# final.net
KiCad netlist of a schematic drawn in Altium Designer
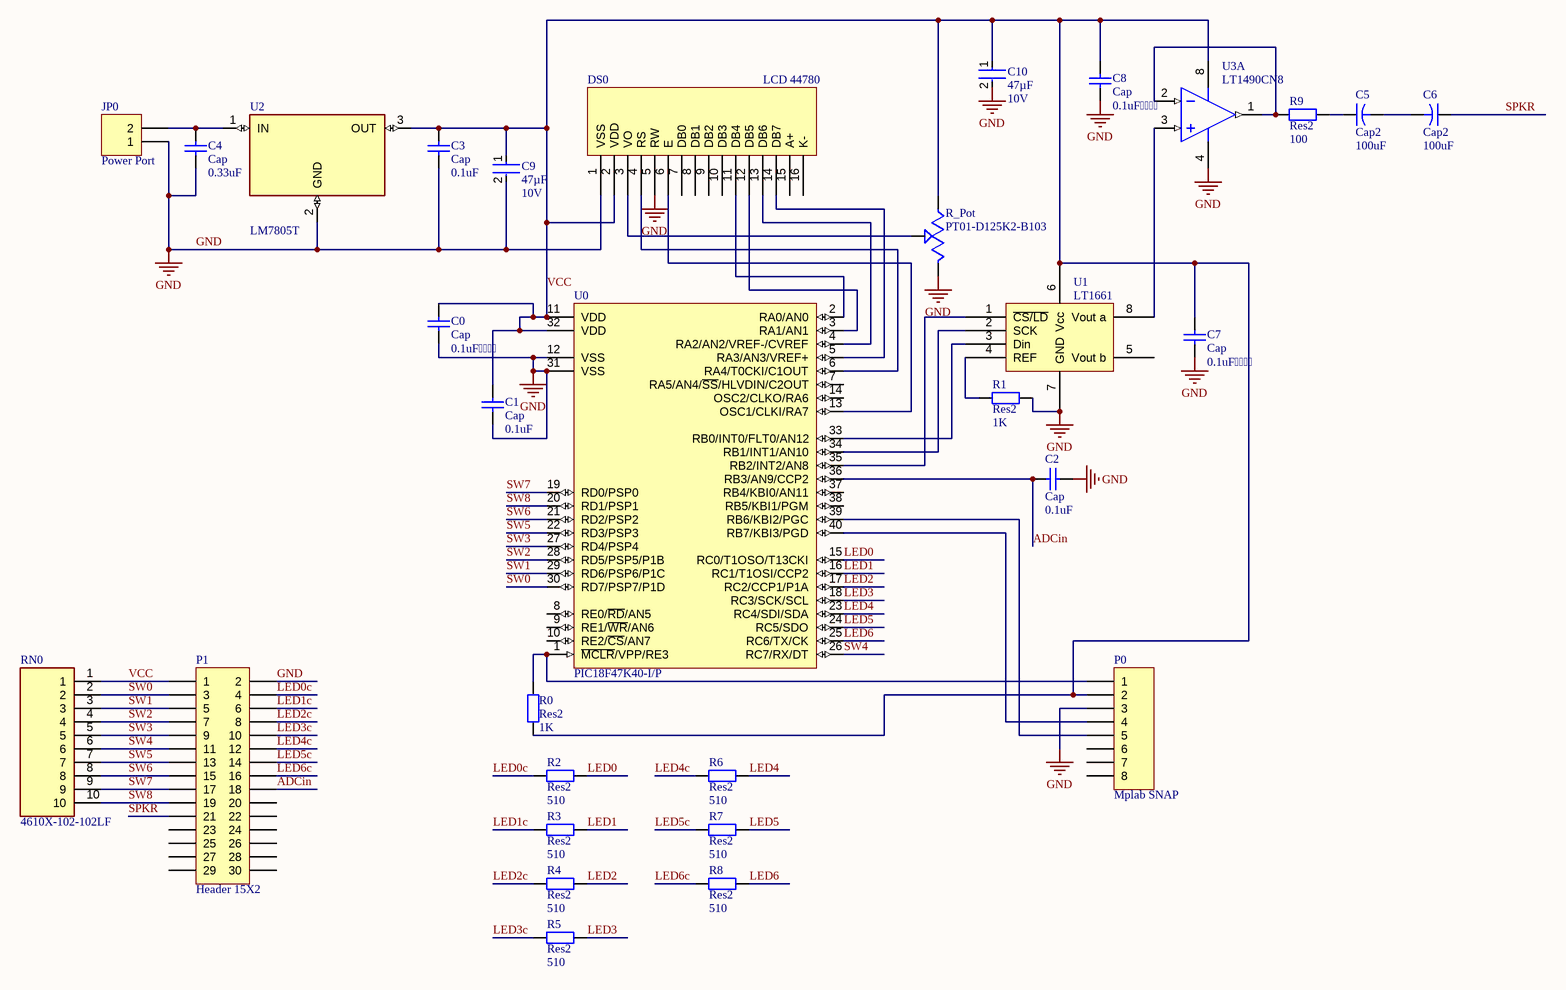
[diagram p0: final.SchDoc]

(export (version "E")
  (design (tool "Eeschema 10.0.6"))
  (components
    (comp (ref "C0")
      (value "Cap")
      (footprint "RAD-0.3")
      (description "Capacitor")
      (fields (field (name "ALTIUM_VALUE") "0.1uF") (field (name "PUBLISHER") "Altium Limited"))
      (libsource (lib "Miscellaneous Devices") (part "Cap"))
    )
    (comp (ref "C1")
      (value "Cap")
      (footprint "RAD-0.3")
      (description "Capacitor")
      (fields (field (name "ALTIUM_VALUE") "0.1uF") (field (name "PUBLISHER") "Altium Limited"))
      (libsource (lib "Miscellaneous Devices") (part "Cap"))
    )
    (comp (ref "C2")
      (value "Cap")
      (footprint "RAD-0.3")
      (description "Capacitor")
      (fields (field (name "ALTIUM_VALUE") "0.1uF") (field (name "PUBLISHER") "Altium Limited"))
      (libsource (lib "Miscellaneous Devices") (part "Cap"))
    )
    (comp (ref "C3")
      (value "Cap")
      (footprint "RAD-0.3")
      (description "Capacitor")
      (fields (field (name "ALTIUM_VALUE") "0.1uF") (field (name "PUBLISHER") "Altium Limited"))
      (libsource (lib "Miscellaneous Devices") (part "Cap"))
    )
    (comp (ref "C4")
      (value "Cap")
      (footprint "RAD-0.3")
      (description "Capacitor")
      (fields (field (name "ALTIUM_VALUE") "0.33uF") (field (name "PUBLISHER") "Altium Limited"))
      (libsource (lib "Miscellaneous Devices") (part "Cap"))
    )
    (comp (ref "C5")
      (value "Cap2")
      (footprint "CAPR5-4X5")
      (description "Capacitor")
      (fields (field (name "ALTIUM_VALUE") "100uF") (field (name "PUBLISHER") "Altium Limited"))
      (libsource (lib "Miscellaneous Devices") (part "Cap2"))
    )
    (comp (ref "C6")
      (value "Cap2")
      (footprint "CAPR5-4X5")
      (description "Capacitor")
      (fields (field (name "ALTIUM_VALUE") "100uF") (field (name "PUBLISHER") "Altium Limited"))
      (libsource (lib "Miscellaneous Devices") (part "Cap2"))
    )
    (comp (ref "C7")
      (value "Cap")
      (footprint "RAD-0.3")
      (description "Capacitor")
      (fields (field (name "ALTIUM_VALUE") "0.1uF") (field (name "PUBLISHER") "Altium Limited"))
      (libsource (lib "Miscellaneous Devices") (part "Cap"))
    )
    (comp (ref "C8")
      (value "Cap")
      (footprint "RAD-0.3")
      (description "Capacitor")
      (fields (field (name "ALTIUM_VALUE") "0.1uF") (field (name "PUBLISHER") "Altium Limited"))
      (libsource (lib "Miscellaneous Devices") (part "Cap"))
    )
    (comp (ref "C9")
      (value "Cap_Kemet_C1206C476M8PACTU_eec")
      (footprint "Kemet_C1206C476M8PACTU_0")
      (description "CAP 47µF ±20% 10V Ceramic Capacitor X5R 1206 (3216 Metric)")
      (fields
        (field (name "CAPACITANCE") "47µF")
        (field (name "VOLTAGE") "10V")
        (field (name "PART NUMBER") "C1206C476M8PACTU")
        (field (name "MANUFACTURER") "Kemet")
      )
      (libsource (lib "Cap_Kemet_C1206C476M8PACTU_eec") (part "Cap_Kemet_C1206C476M8PACTU_eec"))
    )
    (comp (ref "C10")
      (value "Cap_Kemet_C1206C476M8PACTU_eec")
      (footprint "Kemet_C1206C476M8PACTU_0")
      (description "CAP 47µF ±20% 10V Ceramic Capacitor X5R 1206 (3216 Metric)")
      (fields
        (field (name "CAPACITANCE") "47µF")
        (field (name "VOLTAGE") "10V")
        (field (name "PART NUMBER") "C1206C476M8PACTU")
        (field (name "MANUFACTURER") "Kemet")
      )
      (libsource (lib "Cap_Kemet_C1206C476M8PACTU_eec") (part "Cap_Kemet_C1206C476M8PACTU_eec"))
    )
    (comp (ref "DS0")
      (value "LCD 44780")
      (footprint "OLED 16x2")
      (libsource (lib "ECE LIB 21") (part "LCD 44780"))
    )
    (comp (ref "JP0")
      (value "Power Port")
      (footprint "CON2screw")
      (libsource (lib "ECE LIB 21") (part "Power"))
    )
    (comp (ref "P0")
      (value "Mplab SNAP")
      (footprint "HDR1X8")
      (description "Header, 8-Pin")
      (fields (field (name "PUBLISHER") "Altium Limited"))
      (libsource (lib "ECE LIB 21") (part "Header 8"))
    )
    (comp (ref "P1")
      (value "Header 15X2")
      (footprint "HDR2X15")
      (description "Header, 15-Pin, Dual row")
      (fields (field (name "PUBLISHER") "Altium Limited"))
      (libsource (lib "Miscellaneous Connectors") (part "Header 15X2"))
    )
    (comp (ref "R0")
      (value "Res2")
      (footprint "AXIAL-0.4")
      (description "Resistor")
      (fields (field (name "ALTIUM_VALUE") "1K") (field (name "PUBLISHER") "Altium Limited"))
      (libsource (lib "") (part "Res2_1"))
    )
    (comp (ref "R1")
      (value "Res2")
      (footprint "AXIAL-0.4")
      (description "Resistor")
      (fields (field (name "ALTIUM_VALUE") "1K") (field (name "PUBLISHER") "Altium Limited"))
      (libsource (lib "Miscellaneous Devices") (part "Res2"))
    )
    (comp (ref "R2")
      (value "Res2")
      (footprint "AXIAL-0.4")
      (description "Resistor")
      (fields (field (name "ALTIUM_VALUE") "510") (field (name "PUBLISHER") "Altium Limited"))
      (libsource (lib "Miscellaneous Devices") (part "Res2"))
    )
    (comp (ref "R3")
      (value "Res2")
      (footprint "AXIAL-0.4")
      (description "Resistor")
      (fields (field (name "ALTIUM_VALUE") "510") (field (name "PUBLISHER") "Altium Limited"))
      (libsource (lib "Miscellaneous Devices") (part "Res2"))
    )
    (comp (ref "R4")
      (value "Res2")
      (footprint "AXIAL-0.4")
      (description "Resistor")
      (fields (field (name "ALTIUM_VALUE") "510") (field (name "PUBLISHER") "Altium Limited"))
      (libsource (lib "Miscellaneous Devices") (part "Res2"))
    )
    (comp (ref "R5")
      (value "Res2")
      (footprint "AXIAL-0.4")
      (description "Resistor")
      (fields (field (name "ALTIUM_VALUE") "510") (field (name "PUBLISHER") "Altium Limited"))
      (libsource (lib "Miscellaneous Devices") (part "Res2"))
    )
    (comp (ref "R6")
      (value "Res2")
      (footprint "AXIAL-0.4")
      (description "Resistor")
      (fields (field (name "ALTIUM_VALUE") "510") (field (name "PUBLISHER") "Altium Limited"))
      (libsource (lib "Miscellaneous Devices") (part "Res2"))
    )
    (comp (ref "R7")
      (value "Res2")
      (footprint "AXIAL-0.4")
      (description "Resistor")
      (fields (field (name "ALTIUM_VALUE") "510") (field (name "PUBLISHER") "Altium Limited"))
      (libsource (lib "Miscellaneous Devices") (part "Res2"))
    )
    (comp (ref "R8")
      (value "Res2")
      (footprint "AXIAL-0.4")
      (description "Resistor")
      (fields (field (name "ALTIUM_VALUE") "510") (field (name "PUBLISHER") "Altium Limited"))
      (libsource (lib "Miscellaneous Devices") (part "Res2"))
    )
    (comp (ref "R9")
      (value "Res2")
      (footprint "AXIAL-0.4")
      (description "Resistor")
      (fields (field (name "ALTIUM_VALUE") "100") (field (name "PUBLISHER") "Altium Limited"))
      (libsource (lib "Miscellaneous Devices") (part "Res2"))
    )
    (comp (ref "RN0")
      (value "4610X-102-102LF")
      (footprint "SamacSys:SIP249W51P254L2535H508Q10P")
      (description "Resistor Network")
      (fields (field (name "MOUSER PART NUMBER") "652-4610X-2LF-1K"))
      (libsource (lib "*") (part "4610X-102-102LF"))
    )
    (comp (ref "R_Pot")
      (value "PT01-D125K2-B103")
      (footprint "TRIM_PT01-D125K2-B103")
      (description "10k Ohm 1 Gang Linear Through Hole Potentiometer None 1.0 Kierros Carbon 0.05W, 1/20W PC Pins")
      (fields (field (name "MF") "CUI Devices"))
      (libsource (lib "PT01-D125K2-B103") (part "PT01-D125K2-B103"))
    )
    (comp (ref "U0")
      (value "PIC18F47K40-I/P")
      (footprint "DIP-40")
      (libsource (lib "ECE LIB 21") (part "PIC18F4620-I/P_1"))
    )
    (comp (ref "U1") (value "LT1661") (footprint "LT-N8") (libsource (lib "ECE LIB 21") (part "LT1661")))
    (comp (ref "U2")
      (value "LM7805T")
      (footprint "TO220")
      (fields (field (name "MF") "Texas Instruments"))
      (libsource (lib "LM7805T") (part "LM7805T"))
    )
    (comp (ref "U3")
      (value "LT1490CN8")
      (footprint "LT-N8-8")
      (fields
        (field (name "LINEAR TECHNOLOGY PART NUMBER") "LT1490A")
        (field (name "MANUFACTURER") "Linear Technology")
      )
      (libsource (lib "Linear Technology Operational Amplifiers (LT1001-LT1999)") (part "LT1490CN8"))
    )
  )
  (nets
    (net (code "1") (name "/ADCin") (class "Default")
      (node (ref "C2") (pin "2") (pinfunction "2_2") (pintype "passive"))
      (node (ref "P1") (pin "18") (pinfunction "18_18") (pintype "passive"))
      (node (ref "U0") (pin "36") (pinfunction "RB3/AN9/CCP2_36") (pintype "bidirectional"))
    )
    (net (code "2") (name "/LED0") (class "Default")
      (node (ref "R2") (pin "2") (pinfunction "2_2") (pintype "passive"))
      (node (ref "U0") (pin "15") (pinfunction "RC0/T1OSO/T13CKI_15") (pintype "bidirectional"))
    )
    (net (code "3") (name "/LED0c") (class "Default")
      (node (ref "P1") (pin "4") (pinfunction "4_4") (pintype "passive"))
      (node (ref "R2") (pin "1") (pinfunction "1_1") (pintype "passive"))
    )
    (net (code "4") (name "/LED1") (class "Default")
      (node (ref "R3") (pin "2") (pinfunction "2_2") (pintype "passive"))
      (node (ref "U0") (pin "16") (pinfunction "RC1/T1OSI/CCP2_16") (pintype "bidirectional"))
    )
    (net (code "5") (name "/LED1c") (class "Default")
      (node (ref "P1") (pin "6") (pinfunction "6_6") (pintype "passive"))
      (node (ref "R3") (pin "1") (pinfunction "1_1") (pintype "passive"))
    )
    (net (code "6") (name "/LED2") (class "Default")
      (node (ref "R4") (pin "2") (pinfunction "2_2") (pintype "passive"))
      (node (ref "U0") (pin "17") (pinfunction "RC2/CCP1/P1A_17") (pintype "bidirectional"))
    )
    (net (code "7") (name "/LED2c") (class "Default")
      (node (ref "P1") (pin "8") (pinfunction "8_8") (pintype "passive"))
      (node (ref "R4") (pin "1") (pinfunction "1_1") (pintype "passive"))
    )
    (net (code "8") (name "/LED3") (class "Default")
      (node (ref "R5") (pin "2") (pinfunction "2_2") (pintype "passive"))
      (node (ref "U0") (pin "18") (pinfunction "RC3/SCK/SCL_18") (pintype "bidirectional"))
    )
    (net (code "9") (name "/LED3c") (class "Default")
      (node (ref "P1") (pin "10") (pinfunction "10_10") (pintype "passive"))
      (node (ref "R5") (pin "1") (pinfunction "1_1") (pintype "passive"))
    )
    (net (code "10") (name "/LED4") (class "Default")
      (node (ref "R6") (pin "2") (pinfunction "2_2") (pintype "passive"))
      (node (ref "U0") (pin "23") (pinfunction "RC4/SDI/SDA_23") (pintype "bidirectional"))
    )
    (net (code "11") (name "/LED4c") (class "Default")
      (node (ref "P1") (pin "12") (pinfunction "12_12") (pintype "passive"))
      (node (ref "R6") (pin "1") (pinfunction "1_1") (pintype "passive"))
    )
    (net (code "12") (name "/LED5") (class "Default")
      (node (ref "R7") (pin "2") (pinfunction "2_2") (pintype "passive"))
      (node (ref "U0") (pin "24") (pinfunction "RC5/SDO_24") (pintype "bidirectional"))
    )
    (net (code "13") (name "/LED5c") (class "Default")
      (node (ref "P1") (pin "14") (pinfunction "14_14") (pintype "passive"))
      (node (ref "R7") (pin "1") (pinfunction "1_1") (pintype "passive"))
    )
    (net (code "14") (name "/LED6") (class "Default")
      (node (ref "R8") (pin "2") (pinfunction "2_2") (pintype "passive"))
      (node (ref "U0") (pin "25") (pinfunction "RC6/TX/CK_25") (pintype "bidirectional"))
    )
    (net (code "15") (name "/LED6c") (class "Default")
      (node (ref "P1") (pin "16") (pinfunction "16_16") (pintype "passive"))
      (node (ref "R8") (pin "1") (pinfunction "1_1") (pintype "passive"))
    )
    (net (code "16") (name "/SPKR") (class "Default")
      (node (ref "C6") (pin "1") (pinfunction "1_1") (pintype "passive"))
      (node (ref "P1") (pin "21") (pinfunction "21_21") (pintype "passive"))
    )
    (net (code "17") (name "/SW0") (class "Default")
      (node (ref "P1") (pin "3") (pinfunction "3_3") (pintype "passive"))
      (node (ref "RN0") (pin "2") (pinfunction "2_2") (pintype "passive"))
      (node (ref "U0") (pin "30") (pinfunction "RD7/PSP7/P1D_30") (pintype "bidirectional"))
    )
    (net (code "18") (name "/SW1") (class "Default")
      (node (ref "P1") (pin "5") (pinfunction "5_5") (pintype "passive"))
      (node (ref "RN0") (pin "3") (pinfunction "3_3") (pintype "passive"))
      (node (ref "U0") (pin "29") (pinfunction "RD6/PSP6/P1C_29") (pintype "bidirectional"))
    )
    (net (code "19") (name "/SW2") (class "Default")
      (node (ref "P1") (pin "7") (pinfunction "7_7") (pintype "passive"))
      (node (ref "RN0") (pin "4") (pinfunction "4_4") (pintype "passive"))
      (node (ref "U0") (pin "28") (pinfunction "RD5/PSP5/P1B_28") (pintype "bidirectional"))
    )
    (net (code "20") (name "/SW3") (class "Default")
      (node (ref "P1") (pin "9") (pinfunction "9_9") (pintype "passive"))
      (node (ref "RN0") (pin "5") (pinfunction "5_5") (pintype "passive"))
      (node (ref "U0") (pin "27") (pinfunction "RD4/PSP4_27") (pintype "bidirectional"))
    )
    (net (code "21") (name "/SW4") (class "Default")
      (node (ref "P1") (pin "11") (pinfunction "11_11") (pintype "passive"))
      (node (ref "RN0") (pin "6") (pinfunction "6_6") (pintype "passive"))
      (node (ref "U0") (pin "26") (pinfunction "RC7/RX/DT_26") (pintype "bidirectional"))
    )
    (net (code "22") (name "/SW5") (class "Default")
      (node (ref "P1") (pin "13") (pinfunction "13_13") (pintype "passive"))
      (node (ref "RN0") (pin "7") (pinfunction "7_7") (pintype "passive"))
      (node (ref "U0") (pin "22") (pinfunction "RD3/PSP3_22") (pintype "bidirectional"))
    )
    (net (code "23") (name "/SW6") (class "Default")
      (node (ref "P1") (pin "15") (pinfunction "15_15") (pintype "passive"))
      (node (ref "RN0") (pin "8") (pinfunction "8_8") (pintype "passive"))
      (node (ref "U0") (pin "21") (pinfunction "RD2/PSP2_21") (pintype "bidirectional"))
    )
    (net (code "24") (name "/SW7") (class "Default")
      (node (ref "P1") (pin "17") (pinfunction "17_17") (pintype "passive"))
      (node (ref "RN0") (pin "9") (pinfunction "9_9") (pintype "passive"))
      (node (ref "U0") (pin "19") (pinfunction "RD0/PSP0_19") (pintype "bidirectional"))
    )
    (net (code "25") (name "/SW8") (class "Default")
      (node (ref "P1") (pin "19") (pinfunction "19_19") (pintype "passive"))
      (node (ref "RN0") (pin "10") (pinfunction "10_10") (pintype "passive"))
      (node (ref "U0") (pin "20") (pinfunction "RD1/PSP1_20") (pintype "bidirectional"))
    )
    (net (code "26") (name "/VCC") (class "Default")
      (node (ref "C0") (pin "1") (pinfunction "1_1") (pintype "passive"))
      (node (ref "C1") (pin "2") (pinfunction "2_2") (pintype "passive"))
      (node (ref "C10") (pin "1") (pinfunction "1_1") (pintype "passive"))
      (node (ref "C3") (pin "2") (pinfunction "2_2") (pintype "passive"))
      (node (ref "C7") (pin "1") (pinfunction "1_1") (pintype "passive"))
      (node (ref "C8") (pin "1") (pinfunction "1_1") (pintype "passive"))
      (node (ref "C9") (pin "1") (pinfunction "1_1") (pintype "passive"))
      (node (ref "DS0") (pin "2") (pinfunction "VDD_2") (pintype "passive"))
      (node (ref "P0") (pin "2") (pinfunction "2_2") (pintype "passive"))
      (node (ref "P1") (pin "1") (pinfunction "1_1") (pintype "passive"))
      (node (ref "R0") (pin "1") (pinfunction "1_1") (pintype "passive"))
      (node (ref "RN0") (pin "1") (pinfunction "1_1") (pintype "passive"))
      (node (ref "R_Pot") (pin "1") (pinfunction "1_1") (pintype "passive"))
      (node (ref "U0") (pin "11") (pinfunction "VDD_11") (pintype "power_in"))
      (node (ref "U0") (pin "32") (pinfunction "VDD_32") (pintype "power_in"))
      (node (ref "U1") (pin "6") (pinfunction "Vcc_6") (pintype "passive"))
      (node (ref "U2") (pin "3") (pinfunction "OUT_3") (pintype "bidirectional"))
      (node (ref "U3") (pin "8") (pinfunction "V+_8") (pintype "power_in"))
    )
    (net (code "27") (name "GND") (class "Default")
      (node (ref "C0") (pin "2") (pinfunction "2_2") (pintype "passive"))
      (node (ref "C1") (pin "1") (pinfunction "1_1") (pintype "passive"))
      (node (ref "C10") (pin "2") (pinfunction "2_2") (pintype "passive"))
      (node (ref "C2") (pin "1") (pinfunction "1_1") (pintype "passive"))
      (node (ref "C3") (pin "1") (pinfunction "1_1") (pintype "passive"))
      (node (ref "C4") (pin "1") (pinfunction "1_1") (pintype "passive"))
      (node (ref "C7") (pin "2") (pinfunction "2_2") (pintype "passive"))
      (node (ref "C8") (pin "2") (pinfunction "2_2") (pintype "passive"))
      (node (ref "C9") (pin "2") (pinfunction "2_2") (pintype "passive"))
      (node (ref "DS0") (pin "1") (pinfunction "VSS_1") (pintype "passive"))
      (node (ref "DS0") (pin "5") (pinfunction "RW_5") (pintype "passive"))
      (node (ref "JP0") (pin "1") (pinfunction "1_1") (pintype "passive"))
      (node (ref "P0") (pin "3") (pinfunction "3_3") (pintype "passive"))
      (node (ref "P1") (pin "2") (pinfunction "2_2") (pintype "passive"))
      (node (ref "R1") (pin "2") (pinfunction "2_2") (pintype "passive"))
      (node (ref "R_Pot") (pin "3") (pinfunction "3_3") (pintype "passive"))
      (node (ref "U0") (pin "12") (pinfunction "VSS_12") (pintype "power_in"))
      (node (ref "U0") (pin "31") (pinfunction "VSS_31") (pintype "power_in"))
      (node (ref "U1") (pin "7") (pinfunction "GND_7") (pintype "passive"))
      (node (ref "U2") (pin "2") (pinfunction "GND_2") (pintype "bidirectional"))
      (node (ref "U3") (pin "4") (pinfunction "V-_4") (pintype "power_in"))
    )
    (net (code "28") (name "Net-(C5-Pad1)") (class "Default")
      (node (ref "C5") (pin "1") (pinfunction "1_1") (pintype "passive"))
      (node (ref "R9") (pin "2") (pinfunction "2_2") (pintype "passive"))
    )
    (net (code "29") (name "Net-(C5-Pad2)") (class "Default")
      (node (ref "C5") (pin "2") (pinfunction "2_2") (pintype "passive"))
      (node (ref "C6") (pin "2") (pinfunction "2_2") (pintype "passive"))
    )
    (net (code "30") (name "Net-(DS0-DB4)") (class "Default")
      (node (ref "DS0") (pin "11") (pinfunction "DB4_11") (pintype "passive"))
      (node (ref "U0") (pin "2") (pinfunction "RA0/AN0_2") (pintype "bidirectional"))
    )
    (net (code "31") (name "Net-(DS0-DB5)") (class "Default")
      (node (ref "DS0") (pin "12") (pinfunction "DB5_12") (pintype "passive"))
      (node (ref "U0") (pin "3") (pinfunction "RA1/AN1_3") (pintype "bidirectional"))
    )
    (net (code "32") (name "Net-(DS0-DB6)") (class "Default")
      (node (ref "DS0") (pin "13") (pinfunction "DB6_13") (pintype "passive"))
      (node (ref "U0") (pin "4") (pinfunction "RA2/AN2/VREF-/CVREF_4") (pintype "bidirectional"))
    )
    (net (code "33") (name "Net-(DS0-DB7)") (class "Default")
      (node (ref "DS0") (pin "14") (pinfunction "DB7_14") (pintype "passive"))
      (node (ref "U0") (pin "5") (pinfunction "RA3/AN3/VREF+_5") (pintype "bidirectional"))
    )
    (net (code "34") (name "Net-(DS0-E)") (class "Default")
      (node (ref "DS0") (pin "6") (pinfunction "E_6") (pintype "passive"))
      (node (ref "U0") (pin "13") (pinfunction "OSC1/CLKI/RA7_13") (pintype "bidirectional"))
    )
    (net (code "35") (name "Net-(DS0-RS)") (class "Default")
      (node (ref "DS0") (pin "4") (pinfunction "RS_4") (pintype "passive"))
      (node (ref "U0") (pin "6") (pinfunction "RA4/T0CKI/C1OUT_6") (pintype "bidirectional"))
    )
    (net (code "36") (name "Net-(DS0-VO)") (class "Default")
      (node (ref "DS0") (pin "3") (pinfunction "VO_3") (pintype "passive"))
      (node (ref "R_Pot") (pin "2") (pinfunction "2_2") (pintype "passive"))
    )
    (net (code "37") (name "Net-(U0-RB0{slash}INT0{slash}FLT0{slash}AN12)") (class "Default")
      (node (ref "U0") (pin "33") (pinfunction "RB0/INT0/FLT0/AN12_33") (pintype "bidirectional"))
      (node (ref "U1") (pin "3") (pinfunction "Din_3") (pintype "passive"))
    )
    (net (code "38") (name "Net-(U0-RB1{slash}INT1{slash}AN10)") (class "Default")
      (node (ref "U0") (pin "34") (pinfunction "RB1/INT1/AN10_34") (pintype "bidirectional"))
      (node (ref "U1") (pin "2") (pinfunction "SCK_2") (pintype "passive"))
    )
    (net (code "39") (name "Net-(U0-RB2{slash}INT2{slash}AN8)") (class "Default")
      (node (ref "U0") (pin "35") (pinfunction "RB2/INT2/AN8_35") (pintype "bidirectional"))
      (node (ref "U1") (pin "1") (pinfunction "~{CS/LD}_1") (pintype "passive"))
    )
    (net (code "40") (name "Net-(U0-RB6{slash}KBI2{slash}PGC)") (class "Default")
      (node (ref "P0") (pin "5") (pinfunction "5_5") (pintype "passive"))
      (node (ref "U0") (pin "39") (pinfunction "RB6/KBI2/PGC_39") (pintype "bidirectional"))
    )
    (net (code "41") (name "Net-(U0-RB7{slash}KBI3{slash}PGD)") (class "Default")
      (node (ref "P0") (pin "4") (pinfunction "4_4") (pintype "passive"))
      (node (ref "U0") (pin "40") (pinfunction "RB7/KBI3/PGD_40") (pintype "bidirectional"))
    )
    (net (code "42") (name "Net-(U0-~{MCLR}{slash}VPP{slash}RE3)") (class "Default")
      (node (ref "P0") (pin "1") (pinfunction "1_1") (pintype "passive"))
      (node (ref "R0") (pin "2") (pinfunction "2_2") (pintype "passive"))
      (node (ref "U0") (pin "1") (pinfunction "~{MCLR}/VPP/RE3_1") (pintype "input"))
    )
    (net (code "43") (name "Net-(U1-REF)") (class "Default")
      (node (ref "R1") (pin "1") (pinfunction "1_1") (pintype "passive"))
      (node (ref "U1") (pin "4") (pinfunction "REF_4") (pintype "passive"))
    )
    (net (code "44") (name "Net-(U1-Vout_a)") (class "Default")
      (node (ref "U1") (pin "8") (pinfunction "Vout_a_8") (pintype "passive"))
      (node (ref "U3") (pin "3") (pinfunction "+IN_A_3") (pintype "input"))
    )
    (net (code "45") (name "Net-(U2-IN)") (class "Default")
      (node (ref "C4") (pin "2") (pinfunction "2_2") (pintype "passive"))
      (node (ref "JP0") (pin "2") (pinfunction "2_2") (pintype "passive"))
      (node (ref "U2") (pin "1") (pinfunction "IN_1") (pintype "bidirectional"))
    )
    (net (code "46") (name "Net-(U3A--IN_A)") (class "Default")
      (node (ref "R9") (pin "1") (pinfunction "1_1") (pintype "passive"))
      (node (ref "U3") (pin "1") (pinfunction "OUT_A_1") (pintype "output"))
      (node (ref "U3") (pin "2") (pinfunction "-IN_A_2") (pintype "input"))
    )
    (net (code "47") (name "unconnected-(DS0-A+-Pad15)") (class "Default")
      (node (ref "DS0") (pin "15") (pinfunction "A+_15") (pintype "passive"))
    )
    (net (code "48") (name "unconnected-(DS0-DB0-Pad7)") (class "Default")
      (node (ref "DS0") (pin "7") (pinfunction "DB0_7") (pintype "passive"))
    )
    (net (code "49") (name "unconnected-(DS0-DB1-Pad8)") (class "Default")
      (node (ref "DS0") (pin "8") (pinfunction "DB1_8") (pintype "passive"))
    )
    (net (code "50") (name "unconnected-(DS0-DB2-Pad9)") (class "Default")
      (node (ref "DS0") (pin "9") (pinfunction "DB2_9") (pintype "passive"))
    )
    (net (code "51") (name "unconnected-(DS0-DB3-Pad10)") (class "Default")
      (node (ref "DS0") (pin "10") (pinfunction "DB3_10") (pintype "passive"))
    )
    (net (code "52") (name "unconnected-(DS0-K--Pad16)") (class "Default")
      (node (ref "DS0") (pin "16") (pinfunction "K-_16") (pintype "passive"))
    )
    (net (code "53") (name "unconnected-(P0-Pad6)") (class "Default")
      (node (ref "P0") (pin "6") (pinfunction "6_6") (pintype "passive"))
    )
    (net (code "54") (name "unconnected-(P0-Pad7)") (class "Default")
      (node (ref "P0") (pin "7") (pinfunction "7_7") (pintype "passive"))
    )
    (net (code "55") (name "unconnected-(P0-Pad8)") (class "Default")
      (node (ref "P0") (pin "8") (pinfunction "8_8") (pintype "passive"))
    )
    (net (code "56") (name "unconnected-(P1-Pad20)") (class "Default")
      (node (ref "P1") (pin "20") (pinfunction "20_20") (pintype "passive"))
    )
    (net (code "57") (name "unconnected-(P1-Pad22)") (class "Default")
      (node (ref "P1") (pin "22") (pinfunction "22_22") (pintype "passive"))
    )
    (net (code "58") (name "unconnected-(P1-Pad23)") (class "Default")
      (node (ref "P1") (pin "23") (pinfunction "23_23") (pintype "passive"))
    )
    (net (code "59") (name "unconnected-(P1-Pad24)") (class "Default")
      (node (ref "P1") (pin "24") (pinfunction "24_24") (pintype "passive"))
    )
    (net (code "60") (name "unconnected-(P1-Pad25)") (class "Default")
      (node (ref "P1") (pin "25") (pinfunction "25_25") (pintype "passive"))
    )
    (net (code "61") (name "unconnected-(P1-Pad26)") (class "Default")
      (node (ref "P1") (pin "26") (pinfunction "26_26") (pintype "passive"))
    )
    (net (code "62") (name "unconnected-(P1-Pad27)") (class "Default")
      (node (ref "P1") (pin "27") (pinfunction "27_27") (pintype "passive"))
    )
    (net (code "63") (name "unconnected-(P1-Pad28)") (class "Default")
      (node (ref "P1") (pin "28") (pinfunction "28_28") (pintype "passive"))
    )
    (net (code "64") (name "unconnected-(P1-Pad29)") (class "Default")
      (node (ref "P1") (pin "29") (pinfunction "29_29") (pintype "passive"))
    )
    (net (code "65") (name "unconnected-(P1-Pad30)") (class "Default")
      (node (ref "P1") (pin "30") (pinfunction "30_30") (pintype "passive"))
    )
    (net (code "66") (name "unconnected-(U0-OSC2{slash}CLKO{slash}RA6-Pad14)") (class "Default")
      (node (ref "U0") (pin "14") (pinfunction "OSC2/CLKO/RA6_14") (pintype "bidirectional"))
    )
    (net (code "67") (name "unconnected-(U0-RA5{slash}AN4{slash}~{SS}{slash}HLVDIN{slash}C2OUT-Pad7)") (class "Default")
      (node (ref "U0") (pin "7") (pinfunction "RA5/AN4/~{SS}/HLVDIN/C2OUT_7") (pintype "bidirectional"))
    )
    (net (code "68") (name "unconnected-(U0-RB4{slash}KBI0{slash}AN11-Pad37)") (class "Default")
      (node (ref "U0") (pin "37") (pinfunction "RB4/KBI0/AN11_37") (pintype "bidirectional"))
    )
    (net (code "69") (name "unconnected-(U0-RB5{slash}KBI1{slash}PGM-Pad38)") (class "Default")
      (node (ref "U0") (pin "38") (pinfunction "RB5/KBI1/PGM_38") (pintype "bidirectional"))
    )
    (net (code "70") (name "unconnected-(U0-RE0{slash}~{RD}{slash}AN5-Pad8)") (class "Default")
      (node (ref "U0") (pin "8") (pinfunction "RE0/~{RD}/AN5_8") (pintype "bidirectional"))
    )
    (net (code "71") (name "unconnected-(U0-RE1{slash}~{WR}{slash}AN6-Pad9)") (class "Default")
      (node (ref "U0") (pin "9") (pinfunction "RE1/~{WR}/AN6_9") (pintype "bidirectional"))
    )
    (net (code "72") (name "unconnected-(U0-RE2{slash}~{CS}{slash}AN7-Pad10)") (class "Default")
      (node (ref "U0") (pin "10") (pinfunction "RE2/~{CS}/AN7_10") (pintype "bidirectional"))
    )
    (net (code "73") (name "unconnected-(U1-Vout_b-Pad5)") (class "Default")
      (node (ref "U1") (pin "5") (pinfunction "Vout_b_5") (pintype "passive"))
    )
  )
)
